# DAC.net
KiCad netlist of a schematic drawn in Altium Designer
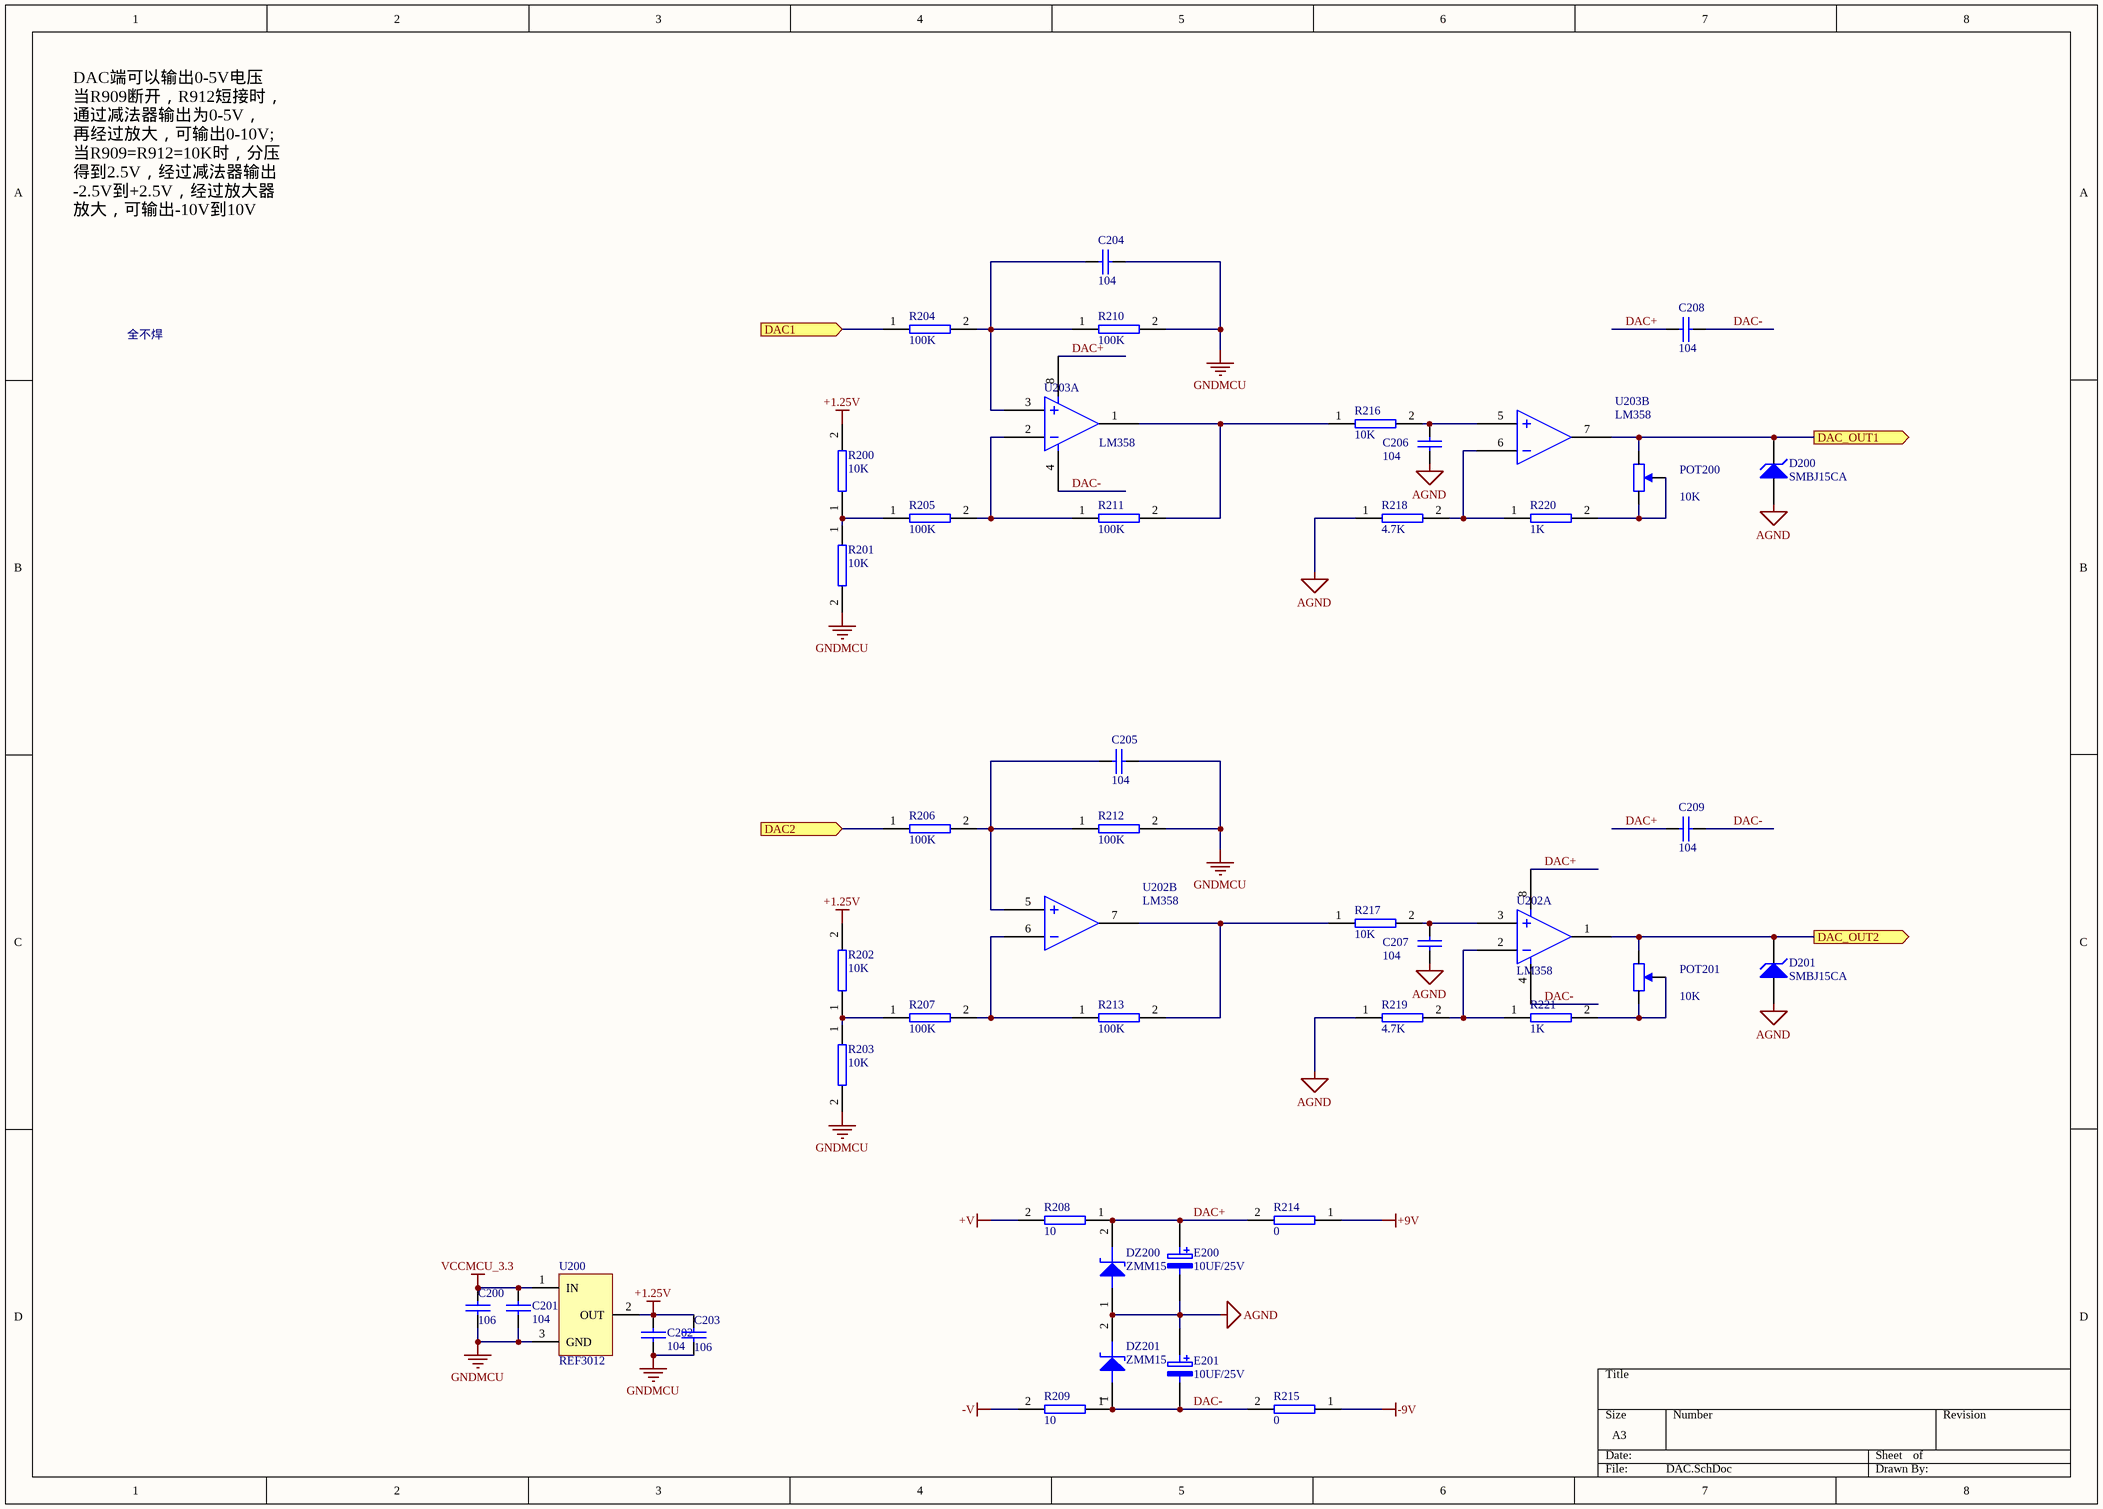
[diagram p0: DAC.SchDoc]

(export (version "E")
  (design (tool "Eeschema 10.0.6"))
  (components
    (comp (ref "C200")
      (value "106")
      (footprint "0805/C2")
      (description "Capacitor")
      (libsource (lib "YGInfoSCHLib") (part "CAP"))
    )
    (comp (ref "C201")
      (value "104")
      (footprint "0805/C2")
      (description "Capacitor")
      (libsource (lib "YGInfoSCHLib") (part "CAP"))
    )
    (comp (ref "C202")
      (value "104")
      (footprint "0805/C2")
      (description "Capacitor")
      (libsource (lib "YGInfoSCHLib") (part "CAP"))
    )
    (comp (ref "C203")
      (value "106")
      (footprint "0805/C2")
      (description "Capacitor")
      (libsource (lib "YGInfoSCHLib") (part "CAP"))
    )
    (comp (ref "C204")
      (value "104")
      (footprint "0805/C2")
      (description "Capacitor")
      (libsource (lib "YGInfoSCHLib") (part "CAP"))
    )
    (comp (ref "C205")
      (value "104")
      (footprint "0805/C2")
      (description "Capacitor")
      (libsource (lib "YGInfoSCHLib") (part "CAP"))
    )
    (comp (ref "C206")
      (value "104")
      (footprint "0805/C2")
      (description "Capacitor")
      (libsource (lib "YGInfoSCHLib") (part "CAP"))
    )
    (comp (ref "C207")
      (value "104")
      (footprint "0805/C2")
      (description "Capacitor")
      (libsource (lib "YGInfoSCHLib") (part "CAP"))
    )
    (comp (ref "C208")
      (value "104")
      (footprint "0805/C2")
      (description "Capacitor")
      (libsource (lib "YGInfoSCHLib") (part "CAP"))
    )
    (comp (ref "C209")
      (value "104")
      (footprint "0805/C2")
      (description "Capacitor")
      (libsource (lib "YGInfoSCHLib") (part "CAP"))
    )
    (comp (ref "D200")
      (value "SMBJ15CA")
      (footprint "SMB")
      (description "Zener Diode")
      (fields (field (name "PUBLISHER") "Altium Limited"))
      (libsource (lib "YGInfoSCHLib") (part "D Zener"))
    )
    (comp (ref "D201")
      (value "SMBJ15CA")
      (footprint "SMB")
      (description "Zener Diode")
      (fields (field (name "PUBLISHER") "Altium Limited"))
      (libsource (lib "YGInfoSCHLib") (part "D Zener"))
    )
    (comp (ref "DZ200")
      (value "ZMM15")
      (footprint "N4148")
      (description "15v/0.5W")
      (libsource (lib "YGInfoSCHLib") (part "ZENER2"))
    )
    (comp (ref "DZ201")
      (value "ZMM15")
      (footprint "N4148")
      (description "15v/0.5W")
      (libsource (lib "YGInfoSCHLib") (part "ZENER2"))
    )
    (comp (ref "E200")
      (value "10UF/25V")
      (footprint "C-10UF")
      (description "Electrolytic Capacitor")
      (libsource (lib "YGInfoSCHLib") (part "ELECTRO2"))
    )
    (comp (ref "E201")
      (value "10UF/25V")
      (footprint "C-10UF")
      (description "Electrolytic Capacitor")
      (libsource (lib "YGInfoSCHLib") (part "ELECTRO2"))
    )
    (comp (ref "POT200")
      (value "10K")
      (footprint "RPOT-3296W")
      (libsource (lib "YGInfoSCHLib") (part "RPOT2"))
    )
    (comp (ref "POT201")
      (value "10K")
      (footprint "rpOT-3296W")
      (libsource (lib "YGInfoSCHLib") (part "RPOT2"))
    )
    (comp (ref "R200")
      (value "10K")
      (footprint "RESC_E0805_2012X50N")
      (libsource (lib "YGInfoSCHLib") (part "RES2"))
    )
    (comp (ref "R201")
      (value "10K")
      (footprint "RESC_E0805_2012X50N")
      (libsource (lib "YGInfoSCHLib") (part "RES2"))
    )
    (comp (ref "R202")
      (value "10K")
      (footprint "RESC_E0805_2012X50N")
      (libsource (lib "YGInfoSCHLib") (part "RES2"))
    )
    (comp (ref "R203")
      (value "10K")
      (footprint "RESC_E0805_2012X50N")
      (libsource (lib "YGInfoSCHLib") (part "RES2"))
    )
    (comp (ref "R204")
      (value "100K")
      (footprint "RESC_E0805_2012X50N")
      (libsource (lib "YGInfoSCHLib") (part "RES2"))
    )
    (comp (ref "R205")
      (value "100K")
      (footprint "RESC_E0805_2012X50N")
      (libsource (lib "YGInfoSCHLib") (part "RES2"))
    )
    (comp (ref "R206")
      (value "100K")
      (footprint "RESC_E0805_2012X50N")
      (libsource (lib "YGInfoSCHLib") (part "RES2"))
    )
    (comp (ref "R207")
      (value "100K")
      (footprint "RESC_E0805_2012X50N")
      (libsource (lib "YGInfoSCHLib") (part "RES2"))
    )
    (comp (ref "R208")
      (value "10")
      (footprint "RESC_E0805_2012X50N")
      (libsource (lib "YGInfoSCHLib") (part "RES2"))
    )
    (comp (ref "R209")
      (value "10")
      (footprint "RESC_E0805_2012X50N")
      (libsource (lib "YGInfoSCHLib") (part "RES2"))
    )
    (comp (ref "R210")
      (value "100K")
      (footprint "RESC_E0805_2012X50N")
      (libsource (lib "YGInfoSCHLib") (part "RES2"))
    )
    (comp (ref "R211")
      (value "100K")
      (footprint "RESC_E0805_2012X50N")
      (libsource (lib "YGInfoSCHLib") (part "RES2"))
    )
    (comp (ref "R212")
      (value "100K")
      (footprint "RESC_E0805_2012X50N")
      (libsource (lib "YGInfoSCHLib") (part "RES2"))
    )
    (comp (ref "R213")
      (value "100K")
      (footprint "RESC_E0805_2012X50N")
      (libsource (lib "YGInfoSCHLib") (part "RES2"))
    )
    (comp (ref "R214")
      (value "0")
      (footprint "RESC_E0805_2012X50N")
      (libsource (lib "YGInfoSCHLib") (part "RES2"))
    )
    (comp (ref "R215")
      (value "0")
      (footprint "RESC_E0805_2012X50N")
      (libsource (lib "YGInfoSCHLib") (part "RES2"))
    )
    (comp (ref "R216")
      (value "10K")
      (footprint "RESC_E0805_2012X50N")
      (libsource (lib "YGInfoSCHLib") (part "RES2"))
    )
    (comp (ref "R217")
      (value "10K")
      (footprint "RESC_E0805_2012X50N")
      (libsource (lib "YGInfoSCHLib") (part "RES2"))
    )
    (comp (ref "R218")
      (value "4.7K")
      (footprint "RESC_E0805_2012X50N")
      (libsource (lib "YGInfoSCHLib") (part "RES2"))
    )
    (comp (ref "R219")
      (value "4.7K")
      (footprint "RESC_E0805_2012X50N")
      (libsource (lib "YGInfoSCHLib") (part "RES2"))
    )
    (comp (ref "R220")
      (value "1K")
      (footprint "RESC_E0805_2012X50N")
      (libsource (lib "YGInfoSCHLib") (part "RES2"))
    )
    (comp (ref "R221")
      (value "1K")
      (footprint "RESC_E0805_2012X50N")
      (libsource (lib "YGInfoSCHLib") (part "RES2"))
    )
    (comp (ref "U200")
      (value "REF3012")
      (footprint "SOT-23")
      (description "2.048V ,HIGH OUTPUT CURRENT: 25mA,HIGH ACCURACY: 0.2%")
      (libsource (lib "YGInfoSCHLib") (part "REF3020"))
    )
    (comp (ref "U202") (value "LM358") (footprint "sO-8") (libsource (lib "YGInfoSCHLib") (part "1458")))
    (comp (ref "U203") (value "LM358") (footprint "so-8") (libsource (lib "YGInfoSCHLib") (part "1458")))
  )
  (nets
    (net (code "1") (name "+1.25V") (class "Default")
      (node (ref "C202") (pin "1") (pinfunction "1_1") (pintype "passive"))
      (node (ref "C203") (pin "2") (pinfunction "2_2") (pintype "passive"))
      (node (ref "R200") (pin "2") (pinfunction "2_2") (pintype "passive"))
      (node (ref "R202") (pin "2") (pinfunction "2_2") (pintype "passive"))
      (node (ref "U200") (pin "2") (pinfunction "OUT_2") (pintype "passive"))
    )
    (net (code "2") (name "+9V") (class "Default")
      (node (ref "R214") (pin "1") (pinfunction "1_1") (pintype "passive"))
    )
    (net (code "3") (name "+V") (class "Default")
      (node (ref "R208") (pin "2") (pinfunction "2_2") (pintype "passive"))
    )
    (net (code "4") (name "-9V") (class "Default")
      (node (ref "R215") (pin "1") (pinfunction "1_1") (pintype "passive"))
    )
    (net (code "5") (name "-V") (class "Default")
      (node (ref "R209") (pin "2") (pinfunction "2_2") (pintype "passive"))
    )
    (net (code "6") (name "/DAC+") (class "Default")
      (node (ref "C208") (pin "1") (pinfunction "1_1") (pintype "passive"))
      (node (ref "C209") (pin "1") (pinfunction "1_1") (pintype "passive"))
      (node (ref "DZ200") (pin "2") (pinfunction "2_2") (pintype "passive"))
      (node (ref "E200") (pin "1") (pinfunction "1_1") (pintype "passive"))
      (node (ref "R208") (pin "1") (pinfunction "1_1") (pintype "passive"))
      (node (ref "R214") (pin "2") (pinfunction "2_2") (pintype "passive"))
      (node (ref "U202") (pin "8") (pintype "passive"))
      (node (ref "U203") (pin "8") (pintype "passive"))
    )
    (net (code "7") (name "/DAC-") (class "Default")
      (node (ref "C208") (pin "2") (pinfunction "2_2") (pintype "passive"))
      (node (ref "C209") (pin "2") (pinfunction "2_2") (pintype "passive"))
      (node (ref "DZ201") (pin "1") (pinfunction "1_1") (pintype "passive"))
      (node (ref "E201") (pin "2") (pinfunction "2_2") (pintype "passive"))
      (node (ref "R209") (pin "1") (pinfunction "1_1") (pintype "passive"))
      (node (ref "R215") (pin "2") (pinfunction "2_2") (pintype "passive"))
      (node (ref "U202") (pin "4") (pintype "passive"))
      (node (ref "U203") (pin "4") (pintype "passive"))
    )
    (net (code "8") (name "/DAC1") (class "Default")
      (node (ref "R204") (pin "1") (pinfunction "1_1") (pintype "passive"))
    )
    (net (code "9") (name "/DAC2") (class "Default")
      (node (ref "R206") (pin "1") (pinfunction "1_1") (pintype "passive"))
    )
    (net (code "10") (name "/DAC_OUT1") (class "Default")
      (node (ref "D200") (pin "2") (pinfunction "K_2") (pintype "passive"))
      (node (ref "POT200") (pin "1") (pinfunction "1_1") (pintype "passive"))
      (node (ref "U203") (pin "7") (pintype "passive"))
    )
    (net (code "11") (name "/DAC_OUT2") (class "Default")
      (node (ref "D201") (pin "2") (pinfunction "K_2") (pintype "passive"))
      (node (ref "POT201") (pin "1") (pinfunction "1_1") (pintype "passive"))
      (node (ref "U202") (pin "1") (pintype "passive"))
    )
    (net (code "12") (name "AGND") (class "Default")
      (node (ref "C206") (pin "1") (pinfunction "1_1") (pintype "passive"))
      (node (ref "C207") (pin "1") (pinfunction "1_1") (pintype "passive"))
      (node (ref "D200") (pin "1") (pinfunction "A_1") (pintype "passive"))
      (node (ref "D201") (pin "1") (pinfunction "A_1") (pintype "passive"))
      (node (ref "DZ200") (pin "1") (pinfunction "1_1") (pintype "passive"))
      (node (ref "DZ201") (pin "2") (pinfunction "2_2") (pintype "passive"))
      (node (ref "E200") (pin "2") (pinfunction "2_2") (pintype "passive"))
      (node (ref "E201") (pin "1") (pinfunction "1_1") (pintype "passive"))
      (node (ref "R218") (pin "1") (pinfunction "1_1") (pintype "passive"))
      (node (ref "R219") (pin "1") (pinfunction "1_1") (pintype "passive"))
    )
    (net (code "13") (name "GNDMCU") (class "Default")
      (node (ref "C200") (pin "1") (pinfunction "1_1") (pintype "passive"))
      (node (ref "C201") (pin "2") (pinfunction "2_2") (pintype "passive"))
      (node (ref "C202") (pin "2") (pinfunction "2_2") (pintype "passive"))
      (node (ref "C203") (pin "1") (pinfunction "1_1") (pintype "passive"))
      (node (ref "C204") (pin "2") (pinfunction "2_2") (pintype "passive"))
      (node (ref "C205") (pin "2") (pinfunction "2_2") (pintype "passive"))
      (node (ref "R201") (pin "2") (pinfunction "2_2") (pintype "passive"))
      (node (ref "R203") (pin "2") (pinfunction "2_2") (pintype "passive"))
      (node (ref "R210") (pin "2") (pinfunction "2_2") (pintype "passive"))
      (node (ref "R212") (pin "2") (pinfunction "2_2") (pintype "passive"))
      (node (ref "U200") (pin "3") (pinfunction "GND_3") (pintype "passive"))
    )
    (net (code "14") (name "Net-(C204-Pad1)") (class "Default")
      (node (ref "C204") (pin "1") (pinfunction "1_1") (pintype "passive"))
      (node (ref "R204") (pin "2") (pinfunction "2_2") (pintype "passive"))
      (node (ref "R210") (pin "1") (pinfunction "1_1") (pintype "passive"))
      (node (ref "U203") (pin "3") (pintype "passive"))
    )
    (net (code "15") (name "Net-(C205-Pad1)") (class "Default")
      (node (ref "C205") (pin "1") (pinfunction "1_1") (pintype "passive"))
      (node (ref "R206") (pin "2") (pinfunction "2_2") (pintype "passive"))
      (node (ref "R212") (pin "1") (pinfunction "1_1") (pintype "passive"))
      (node (ref "U202") (pin "5") (pintype "passive"))
    )
    (net (code "16") (name "Net-(C206-Pad2)") (class "Default")
      (node (ref "C206") (pin "2") (pinfunction "2_2") (pintype "passive"))
      (node (ref "R216") (pin "2") (pinfunction "2_2") (pintype "passive"))
      (node (ref "U203") (pin "5") (pintype "passive"))
    )
    (net (code "17") (name "Net-(C207-Pad2)") (class "Default")
      (node (ref "C207") (pin "2") (pinfunction "2_2") (pintype "passive"))
      (node (ref "R217") (pin "2") (pinfunction "2_2") (pintype "passive"))
      (node (ref "U202") (pin "3") (pintype "passive"))
    )
    (net (code "18") (name "Net-(POT200-Pad2)") (class "Default")
      (node (ref "POT200") (pin "2") (pinfunction "2_2") (pintype "passive"))
      (node (ref "POT200") (pin "3") (pinfunction "3_3") (pintype "passive"))
      (node (ref "R220") (pin "2") (pinfunction "2_2") (pintype "passive"))
    )
    (net (code "19") (name "Net-(POT201-Pad2)") (class "Default")
      (node (ref "POT201") (pin "2") (pinfunction "2_2") (pintype "passive"))
      (node (ref "POT201") (pin "3") (pinfunction "3_3") (pintype "passive"))
      (node (ref "R221") (pin "2") (pinfunction "2_2") (pintype "passive"))
    )
    (net (code "20") (name "Net-(R200-Pad1)") (class "Default")
      (node (ref "R200") (pin "1") (pinfunction "1_1") (pintype "passive"))
      (node (ref "R201") (pin "1") (pinfunction "1_1") (pintype "passive"))
      (node (ref "R205") (pin "1") (pinfunction "1_1") (pintype "passive"))
    )
    (net (code "21") (name "Net-(R202-Pad1)") (class "Default")
      (node (ref "R202") (pin "1") (pinfunction "1_1") (pintype "passive"))
      (node (ref "R203") (pin "1") (pinfunction "1_1") (pintype "passive"))
      (node (ref "R207") (pin "1") (pinfunction "1_1") (pintype "passive"))
    )
    (net (code "22") (name "Net-(R205-Pad2)") (class "Default")
      (node (ref "R205") (pin "2") (pinfunction "2_2") (pintype "passive"))
      (node (ref "R211") (pin "1") (pinfunction "1_1") (pintype "passive"))
      (node (ref "U203") (pin "2") (pintype "passive"))
    )
    (net (code "23") (name "Net-(R207-Pad2)") (class "Default")
      (node (ref "R207") (pin "2") (pinfunction "2_2") (pintype "passive"))
      (node (ref "R213") (pin "1") (pinfunction "1_1") (pintype "passive"))
      (node (ref "U202") (pin "6") (pintype "passive"))
    )
    (net (code "24") (name "Net-(R211-Pad2)") (class "Default")
      (node (ref "R211") (pin "2") (pinfunction "2_2") (pintype "passive"))
      (node (ref "R216") (pin "1") (pinfunction "1_1") (pintype "passive"))
      (node (ref "U203") (pin "1") (pintype "passive"))
    )
    (net (code "25") (name "Net-(R213-Pad2)") (class "Default")
      (node (ref "R213") (pin "2") (pinfunction "2_2") (pintype "passive"))
      (node (ref "R217") (pin "1") (pinfunction "1_1") (pintype "passive"))
      (node (ref "U202") (pin "7") (pintype "passive"))
    )
    (net (code "26") (name "Net-(R218-Pad2)") (class "Default")
      (node (ref "R218") (pin "2") (pinfunction "2_2") (pintype "passive"))
      (node (ref "R220") (pin "1") (pinfunction "1_1") (pintype "passive"))
      (node (ref "U203") (pin "6") (pintype "passive"))
    )
    (net (code "27") (name "Net-(R219-Pad2)") (class "Default")
      (node (ref "R219") (pin "2") (pinfunction "2_2") (pintype "passive"))
      (node (ref "R221") (pin "1") (pinfunction "1_1") (pintype "passive"))
      (node (ref "U202") (pin "2") (pintype "passive"))
    )
    (net (code "28") (name "VCCMCU_3.3") (class "Default")
      (node (ref "C200") (pin "2") (pinfunction "2_2") (pintype "passive"))
      (node (ref "C201") (pin "1") (pinfunction "1_1") (pintype "passive"))
      (node (ref "U200") (pin "1") (pinfunction "IN_1") (pintype "passive"))
    )
  )
)
